# ProProject_stm32F103c8t6_car_board_2024-.net
KiCad netlist of a schematic drawn in EasyEDA Pro
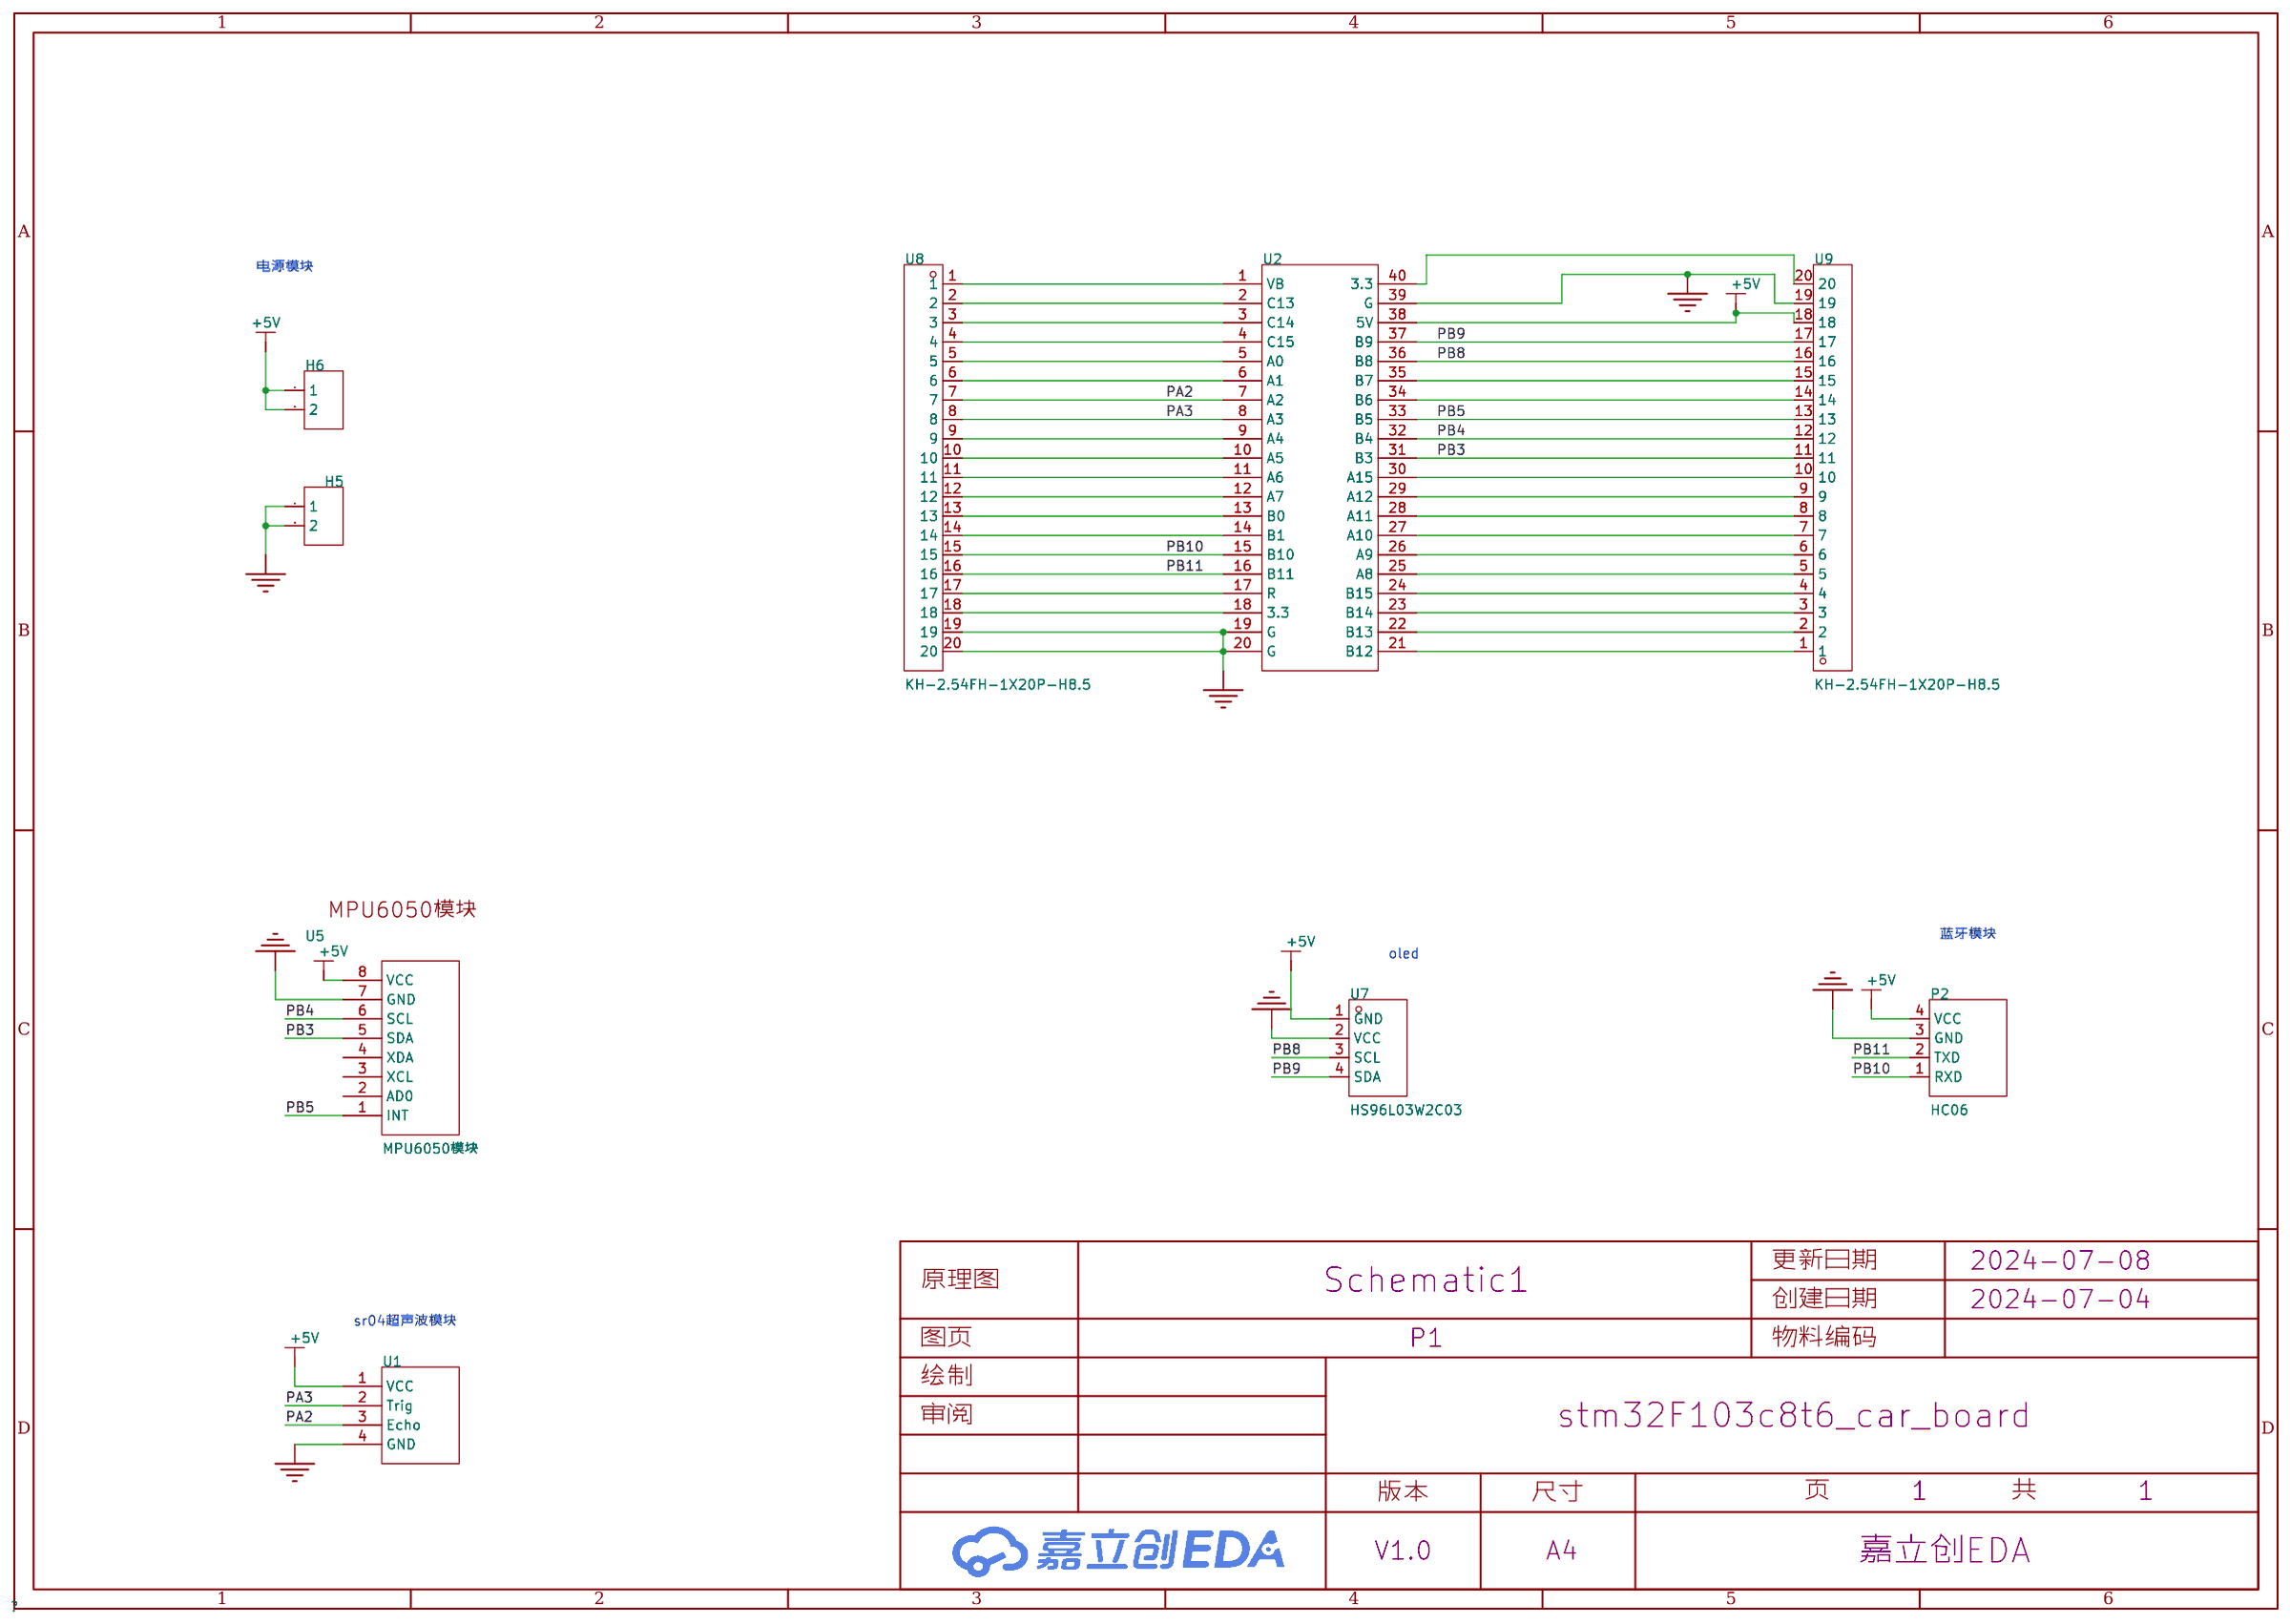
[diagram p0: schematic sheet]

(export (version "E")
  (design (tool "Eeschema 10.0.6"))
  (components
    (comp (ref "H5")
      (value "~")
      (footprint "easyedapro:HDR-TH_2P-P2.54-V-F")
      (libsource (lib "easyedapro") (part "Header-Female-2.54_1x2"))
    )
    (comp (ref "H6")
      (value "~")
      (footprint "easyedapro:HDR-TH_2P-P2.54-V-F")
      (libsource (lib "easyedapro") (part "Header-Female-2.54_1x2"))
    )
    (comp (ref "P2")
      (value "HC06")
      (footprint "easyedapro:HC06")
      (libsource (lib "easyedapro") (part "HC06"))
    )
    (comp (ref "U1")
      (value "~")
      (footprint "easyedapro:HCSR04")
      (libsource (lib "easyedapro") (part "HCSR04"))
    )
    (comp (ref "U2")
      (value "~")
      (footprint "easyedapro:STM32C8T6")
      (libsource (lib "easyedapro") (part "STM32C8T6"))
    )
    (comp (ref "U5")
      (value "MPU6050模块")
      (footprint "easyedapro:MPU6050")
      (libsource (lib "easyedapro") (part "MPU6050模块"))
    )
    (comp (ref "U7")
      (value "HS96L03W2C03")
      (footprint "easyedapro:OLED-TH_L27.8-W27.2-P2.54_C9900033791")
      (description "主控芯片:SSD1315;接口类型:I2C;尺寸(inch):0.96;像素分辨率:128x64;")
      (fields (field (name "Manufacturer") "HS(汉昇)"))
      (libsource (lib "easyedapro") (part "OLED-4PIN"))
    )
    (comp (ref "U8")
      (value "KH-2.54FH-1X20P-H8.5")
      (footprint "easyedapro:HDR-TH_20P-P2.54-V-F-2")
      (fields (field (name "Manufacturer") "kinghelm(金航标)"))
      (libsource (lib "easyedapro") (part "KH-2.54FH-1X20P-H8.5"))
    )
    (comp (ref "U9")
      (value "KH-2.54FH-1X20P-H8.5")
      (footprint "easyedapro:HDR-TH_20P-P2.54-V-F-2")
      (fields (field (name "Manufacturer") "kinghelm(金航标)"))
      (libsource (lib "easyedapro") (part "KH-2.54FH-1X20P-H8.5"))
    )
  )
  (nets
    (net (code "1") (name "+5V") (class "Default")
      (node (ref "H6") (pin "1") (pinfunction "1_1") (pintype "input"))
      (node (ref "H6") (pin "2") (pinfunction "2_2") (pintype "input"))
      (node (ref "P2") (pin "4") (pinfunction "VCC_4") (pintype "unspecified"))
      (node (ref "U1") (pin "1") (pinfunction "VCC_1") (pintype "input"))
      (node (ref "U2") (pin "38") (pinfunction "5V_38") (pintype "input"))
      (node (ref "U5") (pin "8") (pinfunction "VCC_8") (pintype "input"))
      (node (ref "U7") (pin "1") (pinfunction "GND_1") (pintype "unspecified"))
      (node (ref "U9") (pin "18") (pinfunction "18_18") (pintype "unspecified"))
    )
    (net (code "2") (name "/PA2") (class "Default")
      (node (ref "U1") (pin "3") (pinfunction "Echo_3") (pintype "input"))
      (node (ref "U2") (pin "7") (pinfunction "A2_7") (pintype "input"))
      (node (ref "U8") (pin "7") (pinfunction "7_7") (pintype "unspecified"))
    )
    (net (code "3") (name "/PA3") (class "Default")
      (node (ref "U1") (pin "2") (pinfunction "Trig_2") (pintype "input"))
      (node (ref "U2") (pin "8") (pinfunction "A3_8") (pintype "input"))
      (node (ref "U8") (pin "8") (pinfunction "8_8") (pintype "unspecified"))
    )
    (net (code "4") (name "/PB3") (class "Default")
      (node (ref "U2") (pin "31") (pinfunction "B3_31") (pintype "input"))
      (node (ref "U5") (pin "5") (pinfunction "SDA_5") (pintype "input"))
      (node (ref "U9") (pin "11") (pinfunction "11_11") (pintype "unspecified"))
    )
    (net (code "5") (name "/PB4") (class "Default")
      (node (ref "U2") (pin "32") (pinfunction "B4_32") (pintype "input"))
      (node (ref "U5") (pin "6") (pinfunction "SCL_6") (pintype "input"))
      (node (ref "U9") (pin "12") (pinfunction "12_12") (pintype "unspecified"))
    )
    (net (code "6") (name "/PB5") (class "Default")
      (node (ref "U2") (pin "33") (pinfunction "B5_33") (pintype "input"))
      (node (ref "U5") (pin "1") (pinfunction "INT_1") (pintype "input"))
      (node (ref "U9") (pin "13") (pinfunction "13_13") (pintype "unspecified"))
    )
    (net (code "7") (name "/PB8") (class "Default")
      (node (ref "U2") (pin "36") (pinfunction "B8_36") (pintype "input"))
      (node (ref "U7") (pin "3") (pinfunction "SCL_3") (pintype "unspecified"))
      (node (ref "U9") (pin "16") (pinfunction "16_16") (pintype "unspecified"))
    )
    (net (code "8") (name "/PB9") (class "Default")
      (node (ref "U2") (pin "37") (pinfunction "B9_37") (pintype "input"))
      (node (ref "U7") (pin "4") (pinfunction "SDA_4") (pintype "unspecified"))
      (node (ref "U9") (pin "17") (pinfunction "17_17") (pintype "unspecified"))
    )
    (net (code "9") (name "/PB10") (class "Default")
      (node (ref "P2") (pin "1") (pinfunction "RXD_1") (pintype "unspecified"))
      (node (ref "U2") (pin "15") (pinfunction "B10_15") (pintype "input"))
      (node (ref "U8") (pin "15") (pinfunction "15_15") (pintype "unspecified"))
    )
    (net (code "10") (name "/PB11") (class "Default")
      (node (ref "P2") (pin "2") (pinfunction "TXD_2") (pintype "unspecified"))
      (node (ref "U2") (pin "16") (pinfunction "B11_16") (pintype "input"))
      (node (ref "U8") (pin "16") (pinfunction "16_16") (pintype "unspecified"))
    )
    (net (code "11") (name "GND") (class "Default")
      (node (ref "H5") (pin "1") (pinfunction "1_1") (pintype "input"))
      (node (ref "H5") (pin "2") (pinfunction "2_2") (pintype "input"))
      (node (ref "P2") (pin "3") (pinfunction "GND_3") (pintype "unspecified"))
      (node (ref "U1") (pin "4") (pinfunction "GND_4") (pintype "input"))
      (node (ref "U2") (pin "19") (pinfunction "G_19") (pintype "input"))
      (node (ref "U2") (pin "20") (pinfunction "G_20") (pintype "input"))
      (node (ref "U2") (pin "39") (pinfunction "G_39") (pintype "input"))
      (node (ref "U5") (pin "7") (pinfunction "GND_7") (pintype "input"))
      (node (ref "U7") (pin "2") (pinfunction "VCC_2") (pintype "unspecified"))
      (node (ref "U8") (pin "19") (pinfunction "19_19") (pintype "unspecified"))
      (node (ref "U8") (pin "20") (pinfunction "20_20") (pintype "unspecified"))
      (node (ref "U9") (pin "19") (pinfunction "19_19") (pintype "unspecified"))
    )
    (net (code "12") (name "Net-(U2-3.3-Pad18)") (class "Default")
      (node (ref "U2") (pin "18") (pinfunction "3.3_18") (pintype "input"))
      (node (ref "U8") (pin "18") (pinfunction "18_18") (pintype "unspecified"))
    )
    (net (code "13") (name "Net-(U2-3.3-Pad40)") (class "Default")
      (node (ref "U2") (pin "40") (pinfunction "3.3_40") (pintype "input"))
      (node (ref "U9") (pin "20") (pinfunction "20_20") (pintype "unspecified"))
    )
    (net (code "14") (name "Net-(U2-A0)") (class "Default")
      (node (ref "U2") (pin "5") (pinfunction "A0_5") (pintype "input"))
      (node (ref "U8") (pin "5") (pinfunction "5_5") (pintype "unspecified"))
    )
    (net (code "15") (name "Net-(U2-A1)") (class "Default")
      (node (ref "U2") (pin "6") (pinfunction "A1_6") (pintype "input"))
      (node (ref "U8") (pin "6") (pinfunction "6_6") (pintype "unspecified"))
    )
    (net (code "16") (name "Net-(U2-A4)") (class "Default")
      (node (ref "U2") (pin "9") (pinfunction "A4_9") (pintype "input"))
      (node (ref "U8") (pin "9") (pinfunction "9_9") (pintype "unspecified"))
    )
    (net (code "17") (name "Net-(U2-A5)") (class "Default")
      (node (ref "U2") (pin "10") (pinfunction "A5_10") (pintype "input"))
      (node (ref "U8") (pin "10") (pinfunction "10_10") (pintype "unspecified"))
    )
    (net (code "18") (name "Net-(U2-A6)") (class "Default")
      (node (ref "U2") (pin "11") (pinfunction "A6_11") (pintype "input"))
      (node (ref "U8") (pin "11") (pinfunction "11_11") (pintype "unspecified"))
    )
    (net (code "19") (name "Net-(U2-A7)") (class "Default")
      (node (ref "U2") (pin "12") (pinfunction "A7_12") (pintype "input"))
      (node (ref "U8") (pin "12") (pinfunction "12_12") (pintype "unspecified"))
    )
    (net (code "20") (name "Net-(U2-A8)") (class "Default")
      (node (ref "U2") (pin "25") (pinfunction "A8_25") (pintype "input"))
      (node (ref "U9") (pin "5") (pinfunction "5_5") (pintype "unspecified"))
    )
    (net (code "21") (name "Net-(U2-A9)") (class "Default")
      (node (ref "U2") (pin "26") (pinfunction "A9_26") (pintype "input"))
      (node (ref "U9") (pin "6") (pinfunction "6_6") (pintype "unspecified"))
    )
    (net (code "22") (name "Net-(U2-A10)") (class "Default")
      (node (ref "U2") (pin "27") (pinfunction "A10_27") (pintype "input"))
      (node (ref "U9") (pin "7") (pinfunction "7_7") (pintype "unspecified"))
    )
    (net (code "23") (name "Net-(U2-A11)") (class "Default")
      (node (ref "U2") (pin "28") (pinfunction "A11_28") (pintype "input"))
      (node (ref "U9") (pin "8") (pinfunction "8_8") (pintype "unspecified"))
    )
    (net (code "24") (name "Net-(U2-A12)") (class "Default")
      (node (ref "U2") (pin "29") (pinfunction "A12_29") (pintype "input"))
      (node (ref "U9") (pin "9") (pinfunction "9_9") (pintype "unspecified"))
    )
    (net (code "25") (name "Net-(U2-A15)") (class "Default")
      (node (ref "U2") (pin "30") (pinfunction "A15_30") (pintype "input"))
      (node (ref "U9") (pin "10") (pinfunction "10_10") (pintype "unspecified"))
    )
    (net (code "26") (name "Net-(U2-B0)") (class "Default")
      (node (ref "U2") (pin "13") (pinfunction "B0_13") (pintype "input"))
      (node (ref "U8") (pin "13") (pinfunction "13_13") (pintype "unspecified"))
    )
    (net (code "27") (name "Net-(U2-B1)") (class "Default")
      (node (ref "U2") (pin "14") (pinfunction "B1_14") (pintype "input"))
      (node (ref "U8") (pin "14") (pinfunction "14_14") (pintype "unspecified"))
    )
    (net (code "28") (name "Net-(U2-B6)") (class "Default")
      (node (ref "U2") (pin "34") (pinfunction "B6_34") (pintype "input"))
      (node (ref "U9") (pin "14") (pinfunction "14_14") (pintype "unspecified"))
    )
    (net (code "29") (name "Net-(U2-B7)") (class "Default")
      (node (ref "U2") (pin "35") (pinfunction "B7_35") (pintype "input"))
      (node (ref "U9") (pin "15") (pinfunction "15_15") (pintype "unspecified"))
    )
    (net (code "30") (name "Net-(U2-B12)") (class "Default")
      (node (ref "U2") (pin "21") (pinfunction "B12_21") (pintype "input"))
      (node (ref "U9") (pin "1") (pinfunction "1_1") (pintype "unspecified"))
    )
    (net (code "31") (name "Net-(U2-B13)") (class "Default")
      (node (ref "U2") (pin "22") (pinfunction "B13_22") (pintype "input"))
      (node (ref "U9") (pin "2") (pinfunction "2_2") (pintype "unspecified"))
    )
    (net (code "32") (name "Net-(U2-B14)") (class "Default")
      (node (ref "U2") (pin "23") (pinfunction "B14_23") (pintype "input"))
      (node (ref "U9") (pin "3") (pinfunction "3_3") (pintype "unspecified"))
    )
    (net (code "33") (name "Net-(U2-B15)") (class "Default")
      (node (ref "U2") (pin "24") (pinfunction "B15_24") (pintype "input"))
      (node (ref "U9") (pin "4") (pinfunction "4_4") (pintype "unspecified"))
    )
    (net (code "34") (name "Net-(U2-C13)") (class "Default")
      (node (ref "U2") (pin "2") (pinfunction "C13_2") (pintype "input"))
      (node (ref "U8") (pin "2") (pinfunction "2_2") (pintype "unspecified"))
    )
    (net (code "35") (name "Net-(U2-C14)") (class "Default")
      (node (ref "U2") (pin "3") (pinfunction "C14_3") (pintype "input"))
      (node (ref "U8") (pin "3") (pinfunction "3_3") (pintype "unspecified"))
    )
    (net (code "36") (name "Net-(U2-C15)") (class "Default")
      (node (ref "U2") (pin "4") (pinfunction "C15_4") (pintype "input"))
      (node (ref "U8") (pin "4") (pinfunction "4_4") (pintype "unspecified"))
    )
    (net (code "37") (name "Net-(U2-R)") (class "Default")
      (node (ref "U2") (pin "17") (pinfunction "R_17") (pintype "input"))
      (node (ref "U8") (pin "17") (pinfunction "17_17") (pintype "unspecified"))
    )
    (net (code "38") (name "Net-(U2-VB)") (class "Default")
      (node (ref "U2") (pin "1") (pinfunction "VB_1") (pintype "input"))
      (node (ref "U8") (pin "1") (pinfunction "1_1") (pintype "unspecified"))
    )
    (net (code "39") (name "unconnected-(U5-AD0-Pad2)") (class "Default")
      (node (ref "U5") (pin "2") (pinfunction "AD0_2") (pintype "input"))
    )
    (net (code "40") (name "unconnected-(U5-XCL-Pad3)") (class "Default")
      (node (ref "U5") (pin "3") (pinfunction "XCL_3") (pintype "input"))
    )
    (net (code "41") (name "unconnected-(U5-XDA-Pad4)") (class "Default")
      (node (ref "U5") (pin "4") (pinfunction "XDA_4") (pintype "input"))
    )
  )
)
